# Sheet1.net
KiCad netlist of a schematic drawn in Altium Designer
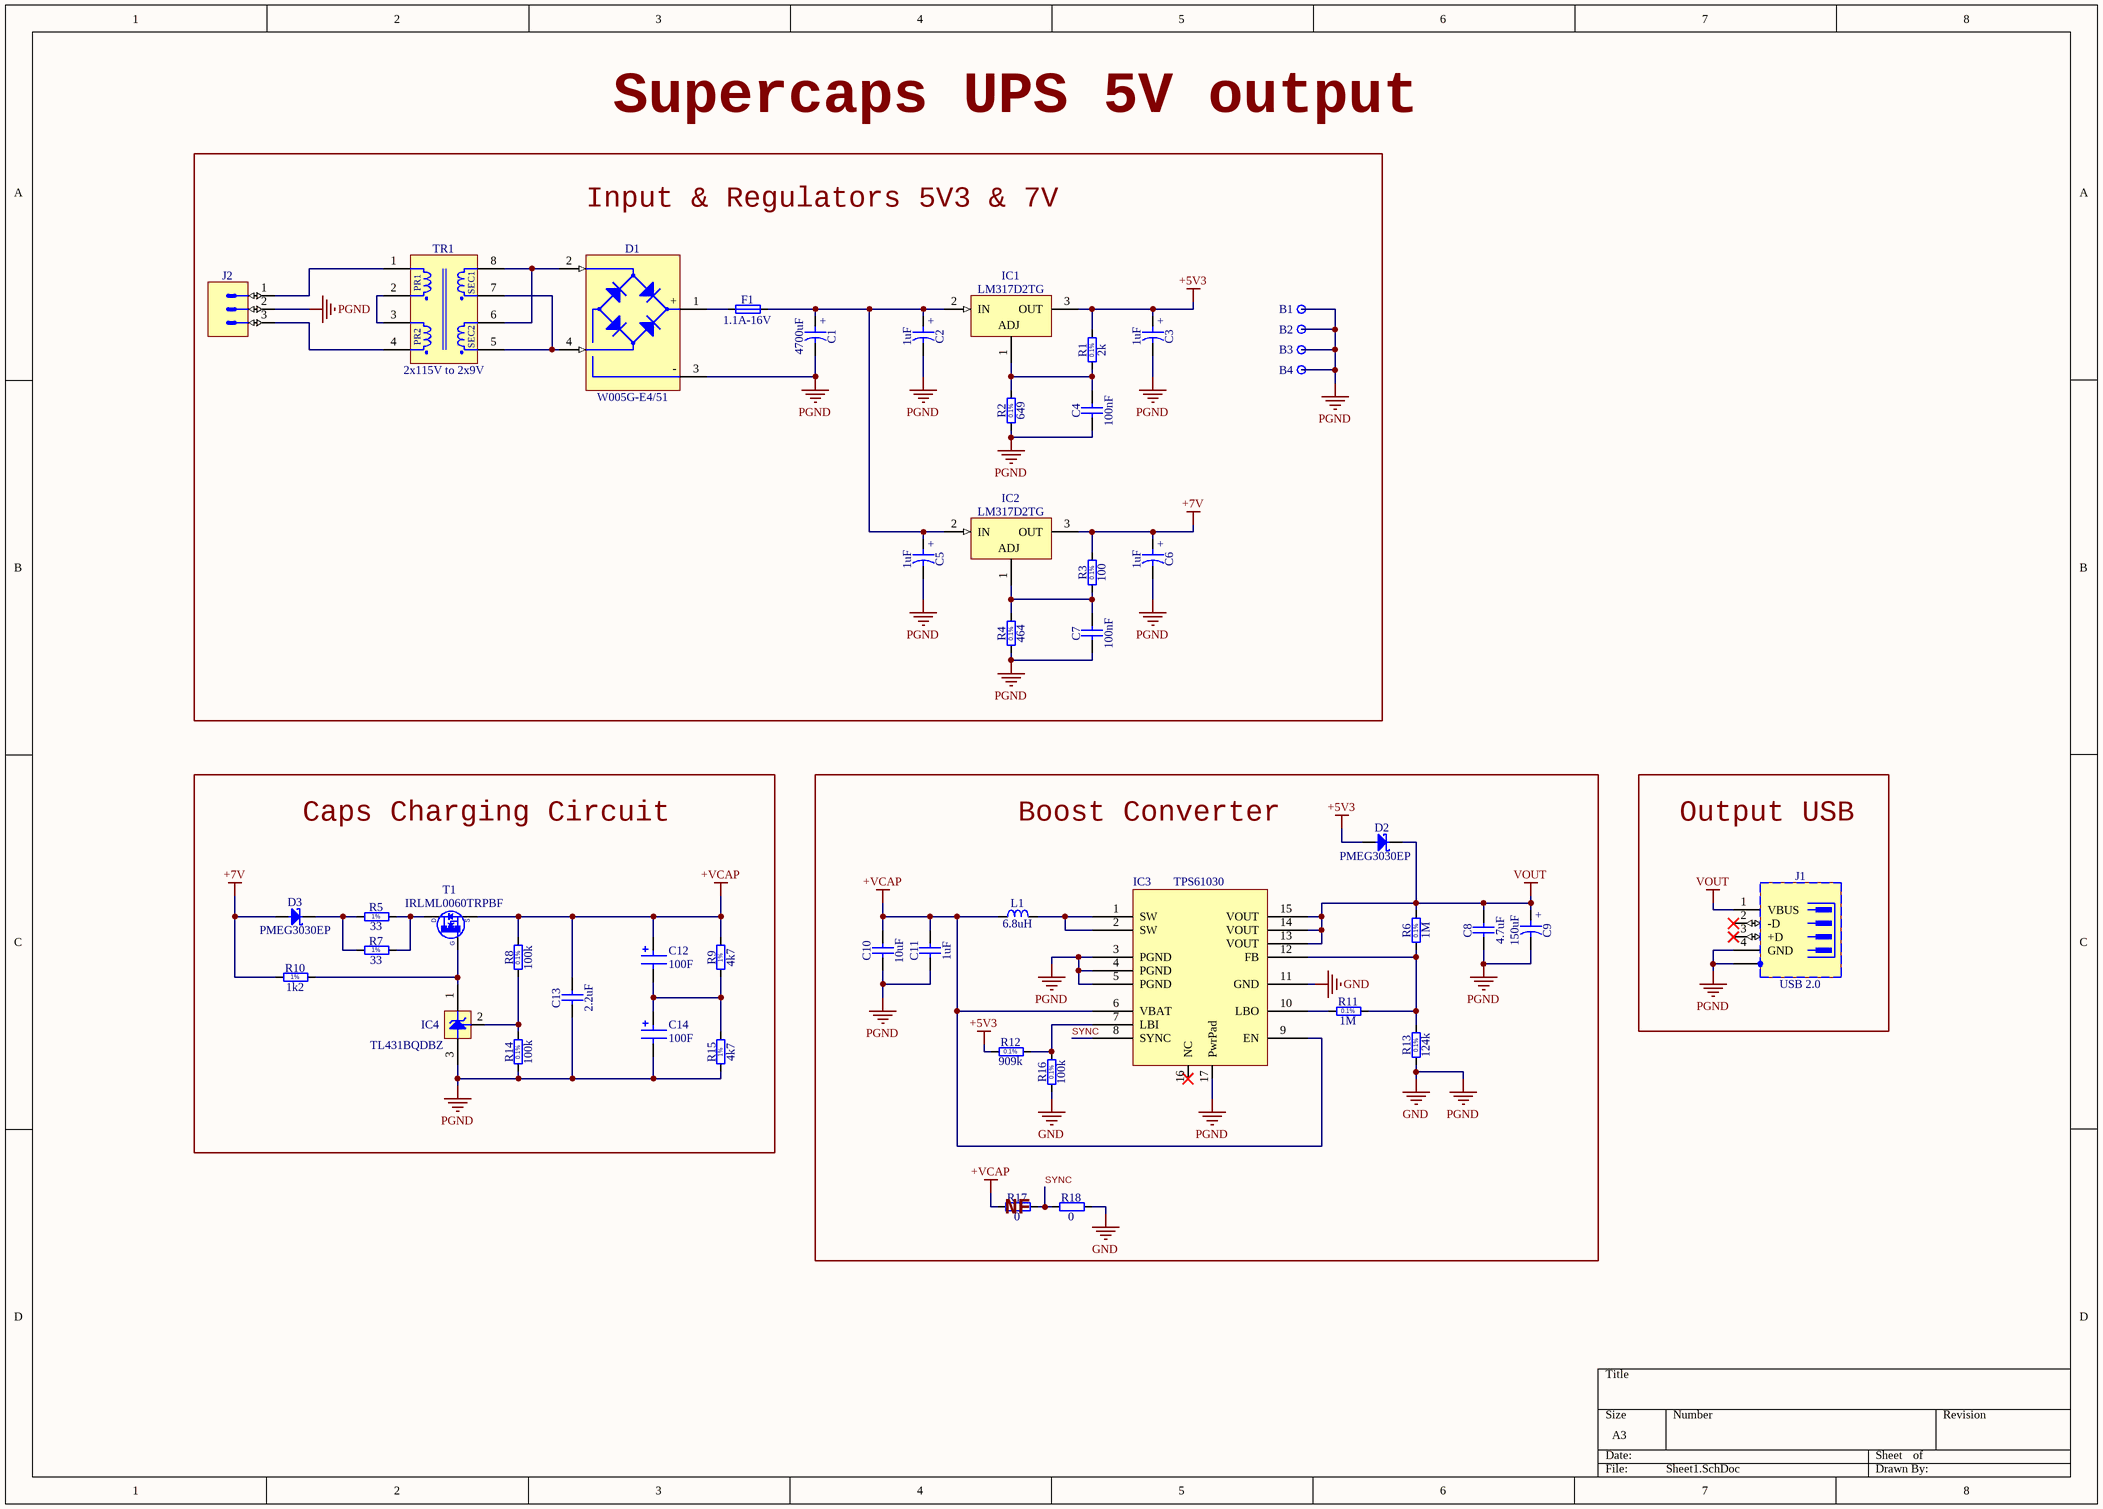
[diagram p0: Sheet1.SchDoc]

(export (version "E")
  (design (tool "Eeschema 10.0.6"))
  (components
    (comp (ref "B1")
      (value "Plated Hole")
      (footprint "MTG240_400")
      (description "Single Terminal Socket")
      (fields (field (name "PART NUMBER") "PLATED_HOLE2.4_PAD4.0") (field (name "AUTHOR") "CERN DEM JMW"))
      (libsource (lib "Eletro-mechanical") (part "Single Terminal Socket"))
    )
    (comp (ref "B2")
      (value "Plated Hole")
      (footprint "MTG240_400")
      (description "Single Terminal Socket")
      (fields (field (name "PART NUMBER") "PLATED_HOLE2.4_PAD4.0") (field (name "AUTHOR") "CERN DEM JMW"))
      (libsource (lib "Eletro-mechanical") (part "Single Terminal Socket"))
    )
    (comp (ref "B3")
      (value "Plated Hole")
      (footprint "MTG240_400")
      (description "Single Terminal Socket")
      (fields (field (name "PART NUMBER") "PLATED_HOLE2.4_PAD4.0") (field (name "AUTHOR") "CERN DEM JMW"))
      (libsource (lib "Eletro-mechanical") (part "Single Terminal Socket"))
    )
    (comp (ref "B4")
      (value "Plated Hole")
      (footprint "MTG240_400")
      (description "Single Terminal Socket")
      (fields (field (name "PART NUMBER") "PLATED_HOLE2.4_PAD4.0") (field (name "AUTHOR") "CERN DEM JMW"))
      (libsource (lib "Eletro-mechanical") (part "Single Terminal Socket"))
    )
    (comp (ref "C1")
      (value "4700uF")
      (footprint "CAPAE1900X1680N")
      (description "Polarised capacitor")
      (fields
        (field (name "PART NUMBER") "CAE1900-1680_4700UF_16V_20%")
        (field (name "VOLTAGE") "16V")
        (field (name "AUTHOR") "CERN DEM JLC")
      )
      (libsource (lib "Capacitors") (part "Capacitor - polarized"))
    )
    (comp (ref "C2")
      (value "1uF")
      (footprint "CAPMP3528X210N")
      (description "Polarised capacitor")
      (fields
        (field (name "PART NUMBER") "CTE3528-21_1UF_35V_10%_LESR2000")
        (field (name "VOLTAGE") "35V")
        (field (name "AUTHOR") "CERN DEM MR")
      )
      (libsource (lib "Capacitors") (part "Capacitor - polarized"))
    )
    (comp (ref "C3")
      (value "1uF")
      (footprint "CAPMP3528X210N")
      (description "Polarised capacitor")
      (fields
        (field (name "PART NUMBER") "CTE3528-21_1UF_35V_10%_LESR2000")
        (field (name "VOLTAGE") "35V")
        (field (name "AUTHOR") "CERN DEM MR")
      )
      (libsource (lib "Capacitors") (part "Capacitor - polarized"))
    )
    (comp (ref "C4")
      (value "100nF")
      (footprint "CAPC2012X88N")
      (description "Non-polarised capacitor")
      (fields
        (field (name "PART NUMBER") "CC0805_100NF_50V_10%_X7R_YUDEN_UMK212B7104KGHT")
        (field (name "VOLTAGE") "50V")
        (field (name "AUTHOR") "CERN DEM JLC")
      )
      (libsource (lib "Capacitors") (part "Capacitor - non polarized"))
    )
    (comp (ref "C5")
      (value "1uF")
      (footprint "CAPMP3528X210N")
      (description "Polarised capacitor")
      (fields
        (field (name "PART NUMBER") "CTE3528-21_1UF_35V_10%_LESR2000")
        (field (name "VOLTAGE") "35V")
        (field (name "AUTHOR") "CERN DEM MR")
      )
      (libsource (lib "Capacitors") (part "Capacitor - polarized"))
    )
    (comp (ref "C6")
      (value "1uF")
      (footprint "CAPMP3528X210N")
      (description "Polarised capacitor")
      (fields
        (field (name "PART NUMBER") "CTE3528-21_1UF_35V_10%_LESR2000")
        (field (name "VOLTAGE") "35V")
        (field (name "AUTHOR") "CERN DEM MR")
      )
      (libsource (lib "Capacitors") (part "Capacitor - polarized"))
    )
    (comp (ref "C7")
      (value "100nF")
      (footprint "CAPC2012X88N")
      (description "Non-polarised capacitor")
      (fields
        (field (name "PART NUMBER") "CC0805_100NF_50V_10%_X7R_YUDEN_UMK212B7104KGHT")
        (field (name "VOLTAGE") "50V")
        (field (name "AUTHOR") "CERN DEM JLC")
      )
      (libsource (lib "Capacitors") (part "Capacitor - non polarized"))
    )
    (comp (ref "C8")
      (value "4.7uF")
      (footprint "CAPC2012X135N")
      (description "Non-polarised capacitor")
      (fields
        (field (name "PART NUMBER") "CC0805_4.7UF_10V_10%_X5R")
        (field (name "VOLTAGE") "10V")
        (field (name "AUTHOR") "CERN DEM JLC")
      )
      (libsource (lib "Capacitors") (part "Capacitor - non polarized"))
    )
    (comp (ref "C9")
      (value "150uF")
      (footprint "CAPMP6032X280N")
      (description "Polarised capacitor")
      (fields
        (field (name "PART NUMBER") "CTE6032-28_150UF_10V_10%")
        (field (name "VOLTAGE") "10V")
        (field (name "AUTHOR") "CERN DEM JLC")
      )
      (libsource (lib "Capacitors") (part "Capacitor - polarized"))
    )
    (comp (ref "C10")
      (value "10uF")
      (footprint "CAPC2012X135N")
      (description "Non-polarised capacitor")
      (fields
        (field (name "PART NUMBER") "CC0805_10UF_16V_10%_X5R")
        (field (name "VOLTAGE") "16V")
        (field (name "AUTHOR") "CERN DEM JLC")
      )
      (libsource (lib "Capacitors") (part "Capacitor - non polarized"))
    )
    (comp (ref "C11")
      (value "1uF")
      (footprint "CAPC2012X135N")
      (description "Non-polarised capacitor")
      (fields
        (field (name "PART NUMBER") "CC0805_1UF_16V_10%_X7R")
        (field (name "VOLTAGE") "16V")
        (field (name "AUTHOR") "CERN DEM JLC")
      )
      (libsource (lib "Capacitors") (part "Capacitor - non polarized"))
    )
    (comp (ref "C12")
      (value "100F")
      (footprint "CAPPR750-1850X4650")
      (description "EECHL0E107")
      (libsource (lib "Schlib1") (part "100F SuperCapacitor"))
    )
    (comp (ref "C13")
      (value "2.2uF")
      (footprint "CAPC2012X140N")
      (description "Non-polarised capacitor")
      (fields
        (field (name "PART NUMBER") "CC0805_2.2UF_16V_10%_X7R_KEMET_C0805C225K4RACAUTO")
        (field (name "VOLTAGE") "16V")
        (field (name "AUTHOR") "CERN DEM MR")
      )
      (libsource (lib "Capacitors") (part "Capacitor - non polarized"))
    )
    (comp (ref "C14")
      (value "100F")
      (footprint "CAPPR750-1850X4650")
      (description "EECHL0E107")
      (libsource (lib "Schlib1") (part "100F SuperCapacitor"))
    )
    (comp (ref "D1")
      (value "W005G-E4/51")
      (footprint "VISHAY_WOG")
      (description "Bridge Rectifier 1+ 2AC 3- 4AC")
      (fields
        (field (name "VOLTAGE") "50V")
        (field (name "POWER") "1.5A")
        (field (name "AUTHOR") "CERN DEM JLC")
      )
      (libsource (lib "ICs And Semiconductors") (part "Bridge Rectifier 1+ 2AC 3- 4AC"))
    )
    (comp (ref "D2")
      (value "PMEG3030EP")
      (footprint "SODFL4725X110N")
      (description "Schottky Diode")
      (fields
        (field (name "VOLTAGE") "30V")
        (field (name "POWER") "3A")
        (field (name "AUTHOR") "CERN DEM JLC")
      )
      (libsource (lib "ICs And Semiconductors") (part "Diode Schottky"))
    )
    (comp (ref "D3")
      (value "PMEG3030EP")
      (footprint "SODFL4725X110N")
      (description "Schottky Diode")
      (fields
        (field (name "VOLTAGE") "30V")
        (field (name "POWER") "3A")
        (field (name "AUTHOR") "CERN DEM JLC")
      )
      (libsource (lib "ICs And Semiconductors") (part "Diode Schottky"))
    )
    (comp (ref "F1")
      (value "1.1A-16V")
      (footprint "FUSR_BOURNS_MF-MSMF_STYLE1(H85)")
      (description "Fuse")
      (fields
        (field (name "PART NUMBER") "FUSR_BOURNS_MF-MSMF110/16-2")
        (field (name "MANUFACTURER") "BOURNS")
        (field (name "AUTHOR") "CERN DEM JLC")
      )
      (libsource (lib "Eletro-mechanical") (part "Fuse"))
    )
    (comp (ref "IC1")
      (value "LM317D2TG")
      (footprint "TO254P1420X457-3N-R795X1023")
      (description "3-Terminal Regulator 1=Adj 2=IN 3=OUT")
      (fields (field (name "MANUFACTURER") "ON SEMICONDUCTOR") (field (name "AUTHOR") "CERN DEM JLC"))
      (libsource (lib "ICs And Semiconductors") (part "REG3 1ADJ-2IN-3OUT"))
    )
    (comp (ref "IC2")
      (value "LM317D2TG")
      (footprint "TO254P1420X457-3N-R795X1023")
      (description "3-Terminal Regulator 1=Adj 2=IN 3=OUT")
      (fields (field (name "MANUFACTURER") "ON SEMICONDUCTOR") (field (name "AUTHOR") "CERN DEM JLC"))
      (libsource (lib "ICs And Semiconductors") (part "REG3 1ADJ-2IN-3OUT"))
    )
    (comp (ref "IC3")
      (value "TPS61030")
      (footprint "SOP65P640X110-17N-S274")
      (description "Boost converter")
      (libsource (lib "Schlib1") (part "TPS61030"))
    )
    (comp (ref "IC4")
      (value "TL431BQDBZ")
      (footprint "SOT95P250X110-3N")
      (description "Precision Reference 1=Cathode 2=Adj 3=Anode")
      (fields (field (name "MANUFACTURER") "NXP SEMICONDUCTORS") (field (name "AUTHOR") "CERN DEM MR"))
      (libsource (lib "ICs And Semiconductors") (part "VREF 1C-2ADJ-3A"))
    )
    (comp (ref "J1")
      (value "USB 2.0")
      (footprint "WURTH_614 104 150 121")
      (description "4 Pin + 1 Shield USB Receptacle")
      (fields
        (field (name "PART NUMBER") "WURTH_614 104 150 121")
        (field (name "MANUFACTURER") "WURTH ELEKTRONIK")
        (field (name "AUTHOR") "CERN DEM JMW")
      )
      (libsource (lib "Connectors") (part "Connector USB 4 Pin + 1Shield"))
    )
    (comp (ref "J2")
      (value "MATE-N-LOK")
      (footprint "TYCO_1-770170-1")
      (description "Connector 3 Male")
      (fields
        (field (name "PART NUMBER") "TYCO_1-770170-1")
        (field (name "MANUFACTURER") "TYCO ELECTRONICS")
        (field (name "AUTHOR") "CERN DEM JLC")
      )
      (libsource (lib "Connectors") (part "Connector 3 Male"))
    )
    (comp (ref "L1")
      (value "6.8uH")
      (footprint "IND_BOURNS_SRU8043")
      (description "Inductor")
      (fields
        (field (name "PART NUMBER") "IND_6.8UH_30%_BOURNS_SRU8043")
        (field (name "POWER") "3.8A")
        (field (name "AUTHOR") "CERN DEM JMW")
      )
      (libsource (lib "Inductors & Transformers") (part "Inductor"))
    )
    (comp (ref "R1")
      (value "2k")
      (footprint "RESC2012X60N")
      (description "Resistor - 0.1%")
      (fields
        (field (name "PART NUMBER") "R0805_2K_0.1%_0.1W_10PPM")
        (field (name "POWER") "0.1W")
        (field (name "AUTHOR") "CERN DEM JLC")
      )
      (libsource (lib "Resistors") (part "Resistor - 0.1%"))
    )
    (comp (ref "R2")
      (value "649")
      (footprint "RESC2012X60N")
      (description "Resistor - 0.1%")
      (fields
        (field (name "PART NUMBER") "R0805_649R_0.1%_0.1W_10PPM")
        (field (name "POWER") "0.1W")
        (field (name "AUTHOR") "CERN DEM JLC")
      )
      (libsource (lib "Resistors") (part "Resistor - 0.1%"))
    )
    (comp (ref "R3")
      (value "100")
      (footprint "RESC2012X60N")
      (description "Resistor - 0.1%")
      (fields
        (field (name "PART NUMBER") "R0805_100R_0.1%_0.1W_10PPM")
        (field (name "POWER") "0.1W")
        (field (name "AUTHOR") "CERN DEM JLC")
      )
      (libsource (lib "Resistors") (part "Resistor - 0.1%"))
    )
    (comp (ref "R4")
      (value "464")
      (footprint "RESC2012X60N")
      (description "Resistor - 0.1%")
      (fields
        (field (name "PART NUMBER") "R0805_464R_0.1%_0.1W_10PPM")
        (field (name "POWER") "0.1W")
        (field (name "AUTHOR") "CERN DEM JLC")
      )
      (libsource (lib "Resistors") (part "Resistor - 0.1%"))
    )
    (comp (ref "R5")
      (value "33")
      (footprint "RESC6331X70N")
      (description "Resistor - 1%")
      (fields
        (field (name "PART NUMBER") "R2512_33R_1%_1W_100PPM")
        (field (name "POWER") "1W")
        (field (name "AUTHOR") "CERN DEM JLC")
      )
      (libsource (lib "Resistors") (part "Resistor - 1%"))
    )
    (comp (ref "R6")
      (value "1M")
      (footprint "RESC2012X60N")
      (description "Resistor - 0.1%")
      (fields
        (field (name "PART NUMBER") "R0805_1M_0.1%_0.1W_25PPM")
        (field (name "POWER") "0.1W")
        (field (name "AUTHOR") "CERN DEM JLC")
      )
      (libsource (lib "Resistors") (part "Resistor - 0.1%"))
    )
    (comp (ref "R7")
      (value "33")
      (footprint "RESC6331X70N")
      (description "Resistor - 1%")
      (fields
        (field (name "PART NUMBER") "R2512_33R_1%_1W_100PPM")
        (field (name "POWER") "1W")
        (field (name "AUTHOR") "CERN DEM JLC")
      )
      (libsource (lib "Resistors") (part "Resistor - 1%"))
    )
    (comp (ref "R8")
      (value "100k")
      (footprint "RESC2012X60N")
      (description "Resistor - 0.1%")
      (fields
        (field (name "PART NUMBER") "R0805_100K_0.1%_0.1W_10PPM")
        (field (name "POWER") "0.1W")
        (field (name "AUTHOR") "CERN DEM JLC")
      )
      (libsource (lib "Resistors") (part "Resistor - 0.1%"))
    )
    (comp (ref "R9")
      (value "4k7")
      (footprint "RESC2012X60N")
      (description "Resistor - 1%")
      (fields
        (field (name "PART NUMBER") "R0805_4K7_1%_0.125W_100PPM")
        (field (name "POWER") "0.125W")
        (field (name "AUTHOR") "CERN DEM JLC")
      )
      (libsource (lib "Resistors") (part "Resistor - 1%"))
    )
    (comp (ref "R10")
      (value "1k2")
      (footprint "RESC2012X60N")
      (description "Resistor - 1%")
      (fields
        (field (name "PART NUMBER") "R0805_1K2_1%_0.125W_100PPM")
        (field (name "POWER") "0.125W")
        (field (name "AUTHOR") "CERN DEM JLC")
      )
      (libsource (lib "Resistors") (part "Resistor - 1%"))
    )
    (comp (ref "R11")
      (value "1M")
      (footprint "RESC2012X60N")
      (description "Resistor - 0.1%")
      (fields
        (field (name "PART NUMBER") "R0805_1M_0.1%_0.1W_25PPM")
        (field (name "POWER") "0.1W")
        (field (name "AUTHOR") "CERN DEM JLC")
      )
      (libsource (lib "Resistors") (part "Resistor - 0.1%"))
    )
    (comp (ref "R12")
      (value "909k")
      (footprint "RESC2012X60N")
      (description "Resistor - 0.1%")
      (fields
        (field (name "PART NUMBER") "R0805_909K_0.1%_0.1W_10PPM")
        (field (name "POWER") "0.1W")
        (field (name "AUTHOR") "CERN DEM MR")
      )
      (libsource (lib "Resistors") (part "Resistor - 0.1%"))
    )
    (comp (ref "R13")
      (value "124k")
      (footprint "RESC2012X60N")
      (description "Resistor - 0.1%")
      (fields
        (field (name "PART NUMBER") "R0805_124K_0.1%_0.1W_10PPM")
        (field (name "POWER") "0.1W")
        (field (name "AUTHOR") "CERN DEM JLC")
      )
      (libsource (lib "Resistors") (part "Resistor - 0.1%"))
    )
    (comp (ref "R14")
      (value "100k")
      (footprint "RESC2012X60N")
      (description "Resistor - 0.1%")
      (fields
        (field (name "PART NUMBER") "R0805_100K_0.1%_0.1W_10PPM")
        (field (name "POWER") "0.1W")
        (field (name "AUTHOR") "CERN DEM JLC")
      )
      (libsource (lib "Resistors") (part "Resistor - 0.1%"))
    )
    (comp (ref "R15")
      (value "4k7")
      (footprint "RESC2012X60N")
      (description "Resistor - 1%")
      (fields
        (field (name "PART NUMBER") "R0805_4K7_1%_0.125W_100PPM")
        (field (name "POWER") "0.125W")
        (field (name "AUTHOR") "CERN DEM JLC")
      )
      (libsource (lib "Resistors") (part "Resistor - 1%"))
    )
    (comp (ref "R16")
      (value "100k")
      (footprint "RESC2012X60N")
      (description "Resistor - 0.1%")
      (fields
        (field (name "PART NUMBER") "R0805_100K_0.1%_0.1W_10PPM")
        (field (name "POWER") "0.1W")
        (field (name "AUTHOR") "CERN DEM JLC")
      )
      (libsource (lib "Resistors") (part "Resistor - 0.1%"))
    )
    (comp (ref "R17")
      (value "0")
      (footprint "RESC2012X60N")
      (description "Resistor")
      (fields
        (field (name "PART NUMBER") "R0805_0R_JUMPER")
        (field (name "MANUFACTURER") "GENERIC")
        (field (name "AUTHOR") "CERN DEM JLC")
      )
      (libsource (lib "Resistors") (part "Resistor"))
    )
    (comp (ref "R18")
      (value "0")
      (footprint "RESC2012X60N")
      (description "Resistor")
      (fields
        (field (name "PART NUMBER") "R0805_0R_JUMPER")
        (field (name "MANUFACTURER") "GENERIC")
        (field (name "AUTHOR") "CERN DEM JLC")
      )
      (libsource (lib "Resistors") (part "Resistor"))
    )
    (comp (ref "T1")
      (value "IRLML0060TRPBF")
      (footprint "SOT95P237X112-3N")
      (description "N-CHANNEL MOSFET WITH DIODE")
      (fields (field (name "MANUFACTURER") "INTERNATIONAL RECTIFIER") (field (name "AUTHOR") "CERN DEM JLC"))
      (libsource (lib "ICs And Semiconductors") (part "N-MOSFET-D 1G 2S 3D"))
    )
    (comp (ref "TR1")
      (value "2x115V to 2x9V")
      (footprint "XFMR_BLOCK_FL6")
      (description "Transformer 2xPrim 2xSec Type1")
      (fields
        (field (name "PART NUMBER") "XFMR_BLOCK_FL6/6")
        (field (name "MANUFACTURER") "BLOCK TRANSFORMATOREN ELEKTRONIK")
        (field (name "AUTHOR") "CERN DEM JLC")
      )
      (libsource (lib "Inductors & Transformers") (part "Transformer 2xPrim 2xSec Type1"))
    )
  )
  (nets
    (net (code "1") (name "+5V3") (class "Default")
      (node (ref "C3") (pin "1") (pinfunction "1_1") (pintype "passive"))
      (node (ref "D2") (pin "2") (pinfunction "A_2") (pintype "passive"))
      (node (ref "IC1") (pin "3") (pinfunction "OUT_3") (pintype "power_in"))
      (node (ref "R1") (pin "2") (pinfunction "2_2") (pintype "passive"))
      (node (ref "R12") (pin "1") (pinfunction "1_1") (pintype "passive"))
    )
    (net (code "2") (name "+7V") (class "Default")
      (node (ref "C6") (pin "1") (pinfunction "1_1") (pintype "passive"))
      (node (ref "D3") (pin "2") (pinfunction "A_2") (pintype "passive"))
      (node (ref "IC2") (pin "3") (pinfunction "OUT_3") (pintype "power_in"))
      (node (ref "R10") (pin "1") (pinfunction "1_1") (pintype "passive"))
      (node (ref "R3") (pin "2") (pinfunction "2_2") (pintype "passive"))
    )
    (net (code "3") (name "+VCAP") (class "Default")
      (node (ref "C10") (pin "2") (pinfunction "2_2") (pintype "passive"))
      (node (ref "C11") (pin "2") (pinfunction "2_2") (pintype "passive"))
      (node (ref "C12") (pin "1") (pinfunction "1_1") (pintype "passive"))
      (node (ref "C13") (pin "2") (pinfunction "2_2") (pintype "passive"))
      (node (ref "IC3") (pin "6") (pinfunction "VBAT_6") (pintype "passive"))
      (node (ref "IC3") (pin "9") (pinfunction "EN_9") (pintype "passive"))
      (node (ref "L1") (pin "1") (pinfunction "1_1") (pintype "passive"))
      (node (ref "R17") (pin "1") (pinfunction "1_1") (pintype "passive"))
      (node (ref "R8") (pin "2") (pinfunction "2_2") (pintype "passive"))
      (node (ref "R9") (pin "2") (pinfunction "2_2") (pintype "passive"))
      (node (ref "T1") (pin "2") (pinfunction "S_2") (pintype "passive"))
    )
    (net (code "4") (name "/SYNC") (class "Default")
      (node (ref "IC3") (pin "8") (pinfunction "SYNC_8") (pintype "passive"))
      (node (ref "R17") (pin "2") (pinfunction "2_2") (pintype "passive"))
      (node (ref "R18") (pin "1") (pinfunction "1_1") (pintype "passive"))
    )
    (net (code "5") (name "GND") (class "Default")
      (node (ref "B1") (pin "1") (pinfunction "1_1") (pintype "bidirectional"))
      (node (ref "B2") (pin "1") (pinfunction "1_1") (pintype "bidirectional"))
      (node (ref "B3") (pin "1") (pinfunction "1_1") (pintype "bidirectional"))
      (node (ref "B4") (pin "1") (pinfunction "1_1") (pintype "bidirectional"))
      (node (ref "C1") (pin "2") (pinfunction "2_2") (pintype "passive"))
      (node (ref "C10") (pin "1") (pinfunction "1_1") (pintype "passive"))
      (node (ref "C11") (pin "1") (pinfunction "1_1") (pintype "passive"))
      (node (ref "C13") (pin "1") (pinfunction "1_1") (pintype "passive"))
      (node (ref "C14") (pin "2") (pinfunction "2_2") (pintype "passive"))
      (node (ref "C2") (pin "2") (pinfunction "2_2") (pintype "passive"))
      (node (ref "C3") (pin "2") (pinfunction "2_2") (pintype "passive"))
      (node (ref "C4") (pin "1") (pinfunction "1_1") (pintype "passive"))
      (node (ref "C5") (pin "2") (pinfunction "2_2") (pintype "passive"))
      (node (ref "C6") (pin "2") (pinfunction "2_2") (pintype "passive"))
      (node (ref "C7") (pin "1") (pinfunction "1_1") (pintype "passive"))
      (node (ref "C8") (pin "1") (pinfunction "1_1") (pintype "passive"))
      (node (ref "C9") (pin "2") (pinfunction "2_2") (pintype "passive"))
      (node (ref "D1") (pin "3") (pinfunction "-_3") (pintype "power_in"))
      (node (ref "IC3") (pin "11") (pinfunction "GND_11") (pintype "passive"))
      (node (ref "IC3") (pin "17") (pinfunction "PwrPad_17") (pintype "passive"))
      (node (ref "IC3") (pin "3") (pinfunction "PGND_3") (pintype "passive"))
      (node (ref "IC3") (pin "4") (pinfunction "PGND_4") (pintype "passive"))
      (node (ref "IC3") (pin "5") (pinfunction "PGND_5") (pintype "passive"))
      (node (ref "IC4") (pin "3") (pinfunction "A_3") (pintype "passive"))
      (node (ref "J1") (pin "4") (pinfunction "GND_4") (pintype "power_in"))
      (node (ref "J1") (pin "5") (pinfunction "SHIELD_5") (pintype "power_in"))
      (node (ref "J2") (pin "2") (pinfunction "2_2") (pintype "bidirectional"))
      (node (ref "R13") (pin "1") (pinfunction "1_1") (pintype "passive"))
      (node (ref "R14") (pin "1") (pinfunction "1_1") (pintype "passive"))
      (node (ref "R15") (pin "1") (pinfunction "1_1") (pintype "passive"))
      (node (ref "R16") (pin "1") (pinfunction "1_1") (pintype "passive"))
      (node (ref "R18") (pin "2") (pinfunction "2_2") (pintype "passive"))
      (node (ref "R2") (pin "1") (pinfunction "1_1") (pintype "passive"))
      (node (ref "R4") (pin "1") (pinfunction "1_1") (pintype "passive"))
    )
    (net (code "6") (name "Net-(C12-Pad2)") (class "Default")
      (node (ref "C12") (pin "2") (pinfunction "2_2") (pintype "passive"))
      (node (ref "C14") (pin "1") (pinfunction "1_1") (pintype "passive"))
      (node (ref "R15") (pin "2") (pinfunction "2_2") (pintype "passive"))
      (node (ref "R9") (pin "1") (pinfunction "1_1") (pintype "passive"))
    )
    (net (code "7") (name "Net-(D1-+)") (class "Default")
      (node (ref "D1") (pin "1") (pinfunction "+_1") (pintype "power_in"))
      (node (ref "F1") (pin "1") (pinfunction "1_1") (pintype "passive"))
    )
    (net (code "8") (name "Net-(D1-AC-Pad2)") (class "Default")
      (node (ref "D1") (pin "2") (pinfunction "AC_2") (pintype "input"))
      (node (ref "TR1") (pin "6") (pinfunction "S2_6") (pintype "passive"))
      (node (ref "TR1") (pin "8") (pinfunction "S1_8") (pintype "passive"))
    )
    (net (code "9") (name "Net-(D1-AC-Pad4)") (class "Default")
      (node (ref "D1") (pin "4") (pinfunction "AC_4") (pintype "input"))
      (node (ref "TR1") (pin "5") (pinfunction "S2_5") (pintype "passive"))
      (node (ref "TR1") (pin "7") (pinfunction "S1_7") (pintype "passive"))
    )
    (net (code "10") (name "Net-(D3-C)") (class "Default")
      (node (ref "D3") (pin "1") (pinfunction "C_1") (pintype "passive"))
      (node (ref "R5") (pin "1") (pinfunction "1_1") (pintype "passive"))
      (node (ref "R7") (pin "1") (pinfunction "1_1") (pintype "passive"))
    )
    (net (code "11") (name "Net-(IC1-ADJ)") (class "Default")
      (node (ref "C4") (pin "2") (pinfunction "2_2") (pintype "passive"))
      (node (ref "IC1") (pin "1") (pinfunction "ADJ_1") (pintype "power_in"))
      (node (ref "R1") (pin "1") (pinfunction "1_1") (pintype "passive"))
      (node (ref "R2") (pin "2") (pinfunction "2_2") (pintype "passive"))
    )
    (net (code "12") (name "Net-(IC1-IN)") (class "Default")
      (node (ref "C1") (pin "1") (pinfunction "1_1") (pintype "passive"))
      (node (ref "C2") (pin "1") (pinfunction "1_1") (pintype "passive"))
      (node (ref "C5") (pin "1") (pinfunction "1_1") (pintype "passive"))
      (node (ref "F1") (pin "2") (pinfunction "2_2") (pintype "passive"))
      (node (ref "IC1") (pin "2") (pinfunction "IN_2") (pintype "input"))
      (node (ref "IC2") (pin "2") (pinfunction "IN_2") (pintype "input"))
    )
    (net (code "13") (name "Net-(IC2-ADJ)") (class "Default")
      (node (ref "C7") (pin "2") (pinfunction "2_2") (pintype "passive"))
      (node (ref "IC2") (pin "1") (pinfunction "ADJ_1") (pintype "power_in"))
      (node (ref "R3") (pin "1") (pinfunction "1_1") (pintype "passive"))
      (node (ref "R4") (pin "2") (pinfunction "2_2") (pintype "passive"))
    )
    (net (code "14") (name "Net-(IC3-FB)") (class "Default")
      (node (ref "IC3") (pin "12") (pinfunction "FB_12") (pintype "passive"))
      (node (ref "R11") (pin "2") (pinfunction "2_2") (pintype "passive"))
      (node (ref "R13") (pin "2") (pinfunction "2_2") (pintype "passive"))
      (node (ref "R6") (pin "1") (pinfunction "1_1") (pintype "passive"))
    )
    (net (code "15") (name "Net-(IC3-LBI)") (class "Default")
      (node (ref "IC3") (pin "7") (pinfunction "LBI_7") (pintype "passive"))
      (node (ref "R12") (pin "2") (pinfunction "2_2") (pintype "passive"))
      (node (ref "R16") (pin "2") (pinfunction "2_2") (pintype "passive"))
    )
    (net (code "16") (name "Net-(IC3-LBO)") (class "Default")
      (node (ref "IC3") (pin "10") (pinfunction "LBO_10") (pintype "passive"))
      (node (ref "R11") (pin "1") (pinfunction "1_1") (pintype "passive"))
    )
    (net (code "17") (name "Net-(IC3-SW-Pad1)") (class "Default")
      (node (ref "IC3") (pin "1") (pinfunction "SW_1") (pintype "passive"))
      (node (ref "IC3") (pin "2") (pinfunction "SW_2") (pintype "passive"))
      (node (ref "L1") (pin "2") (pinfunction "2_2") (pintype "passive"))
    )
    (net (code "18") (name "Net-(IC4-Adj)") (class "Default")
      (node (ref "IC4") (pin "2") (pinfunction "Adj_2") (pintype "passive"))
      (node (ref "R14") (pin "2") (pinfunction "2_2") (pintype "passive"))
      (node (ref "R8") (pin "1") (pinfunction "1_1") (pintype "passive"))
    )
    (net (code "19") (name "Net-(IC4-C)") (class "Default")
      (node (ref "IC4") (pin "1") (pinfunction "C_1") (pintype "passive"))
      (node (ref "R10") (pin "2") (pinfunction "2_2") (pintype "passive"))
      (node (ref "T1") (pin "1") (pinfunction "G_1") (pintype "passive"))
    )
    (net (code "20") (name "Net-(J2-Pad1)") (class "Default")
      (node (ref "J2") (pin "1") (pinfunction "1_1") (pintype "bidirectional"))
      (node (ref "TR1") (pin "1") (pinfunction "P1_1") (pintype "passive"))
    )
    (net (code "21") (name "Net-(J2-Pad3)") (class "Default")
      (node (ref "J2") (pin "3") (pinfunction "3_3") (pintype "bidirectional"))
      (node (ref "TR1") (pin "4") (pinfunction "P2_4") (pintype "passive"))
    )
    (net (code "22") (name "Net-(T1-D)") (class "Default")
      (node (ref "R5") (pin "2") (pinfunction "2_2") (pintype "passive"))
      (node (ref "R7") (pin "2") (pinfunction "2_2") (pintype "passive"))
      (node (ref "T1") (pin "3") (pinfunction "D_3") (pintype "passive"))
    )
    (net (code "23") (name "Net-(TR1-P1-Pad2)") (class "Default")
      (node (ref "TR1") (pin "2") (pinfunction "P1_2") (pintype "passive"))
      (node (ref "TR1") (pin "3") (pinfunction "P2_3") (pintype "passive"))
    )
    (net (code "24") (name "VOUT") (class "Default")
      (node (ref "C8") (pin "2") (pinfunction "2_2") (pintype "passive"))
      (node (ref "C9") (pin "1") (pinfunction "1_1") (pintype "passive"))
      (node (ref "D2") (pin "1") (pinfunction "C_1") (pintype "passive"))
      (node (ref "IC3") (pin "13") (pinfunction "VOUT_13") (pintype "passive"))
      (node (ref "IC3") (pin "14") (pinfunction "VOUT_14") (pintype "passive"))
      (node (ref "IC3") (pin "15") (pinfunction "VOUT_15") (pintype "passive"))
      (node (ref "J1") (pin "1") (pinfunction "VBUS_1") (pintype "power_in"))
      (node (ref "R6") (pin "2") (pinfunction "2_2") (pintype "passive"))
    )
    (net (code "25") (name "unconnected-(IC3-NC-Pad16)") (class "Default")
      (node (ref "IC3") (pin "16") (pinfunction "NC_16") (pintype "passive+no_connect"))
    )
    (net (code "26") (name "unconnected-(J1-+D-Pad3)") (class "Default")
      (node (ref "J1") (pin "3") (pinfunction "+D_3") (pintype "bidirectional+no_connect"))
    )
    (net (code "27") (name "unconnected-(J1--D-Pad2)") (class "Default")
      (node (ref "J1") (pin "2") (pinfunction "-D_2") (pintype "bidirectional+no_connect"))
    )
  )
)
